# ac_thing.net
KiCad netlist of a schematic drawn in EAGLE
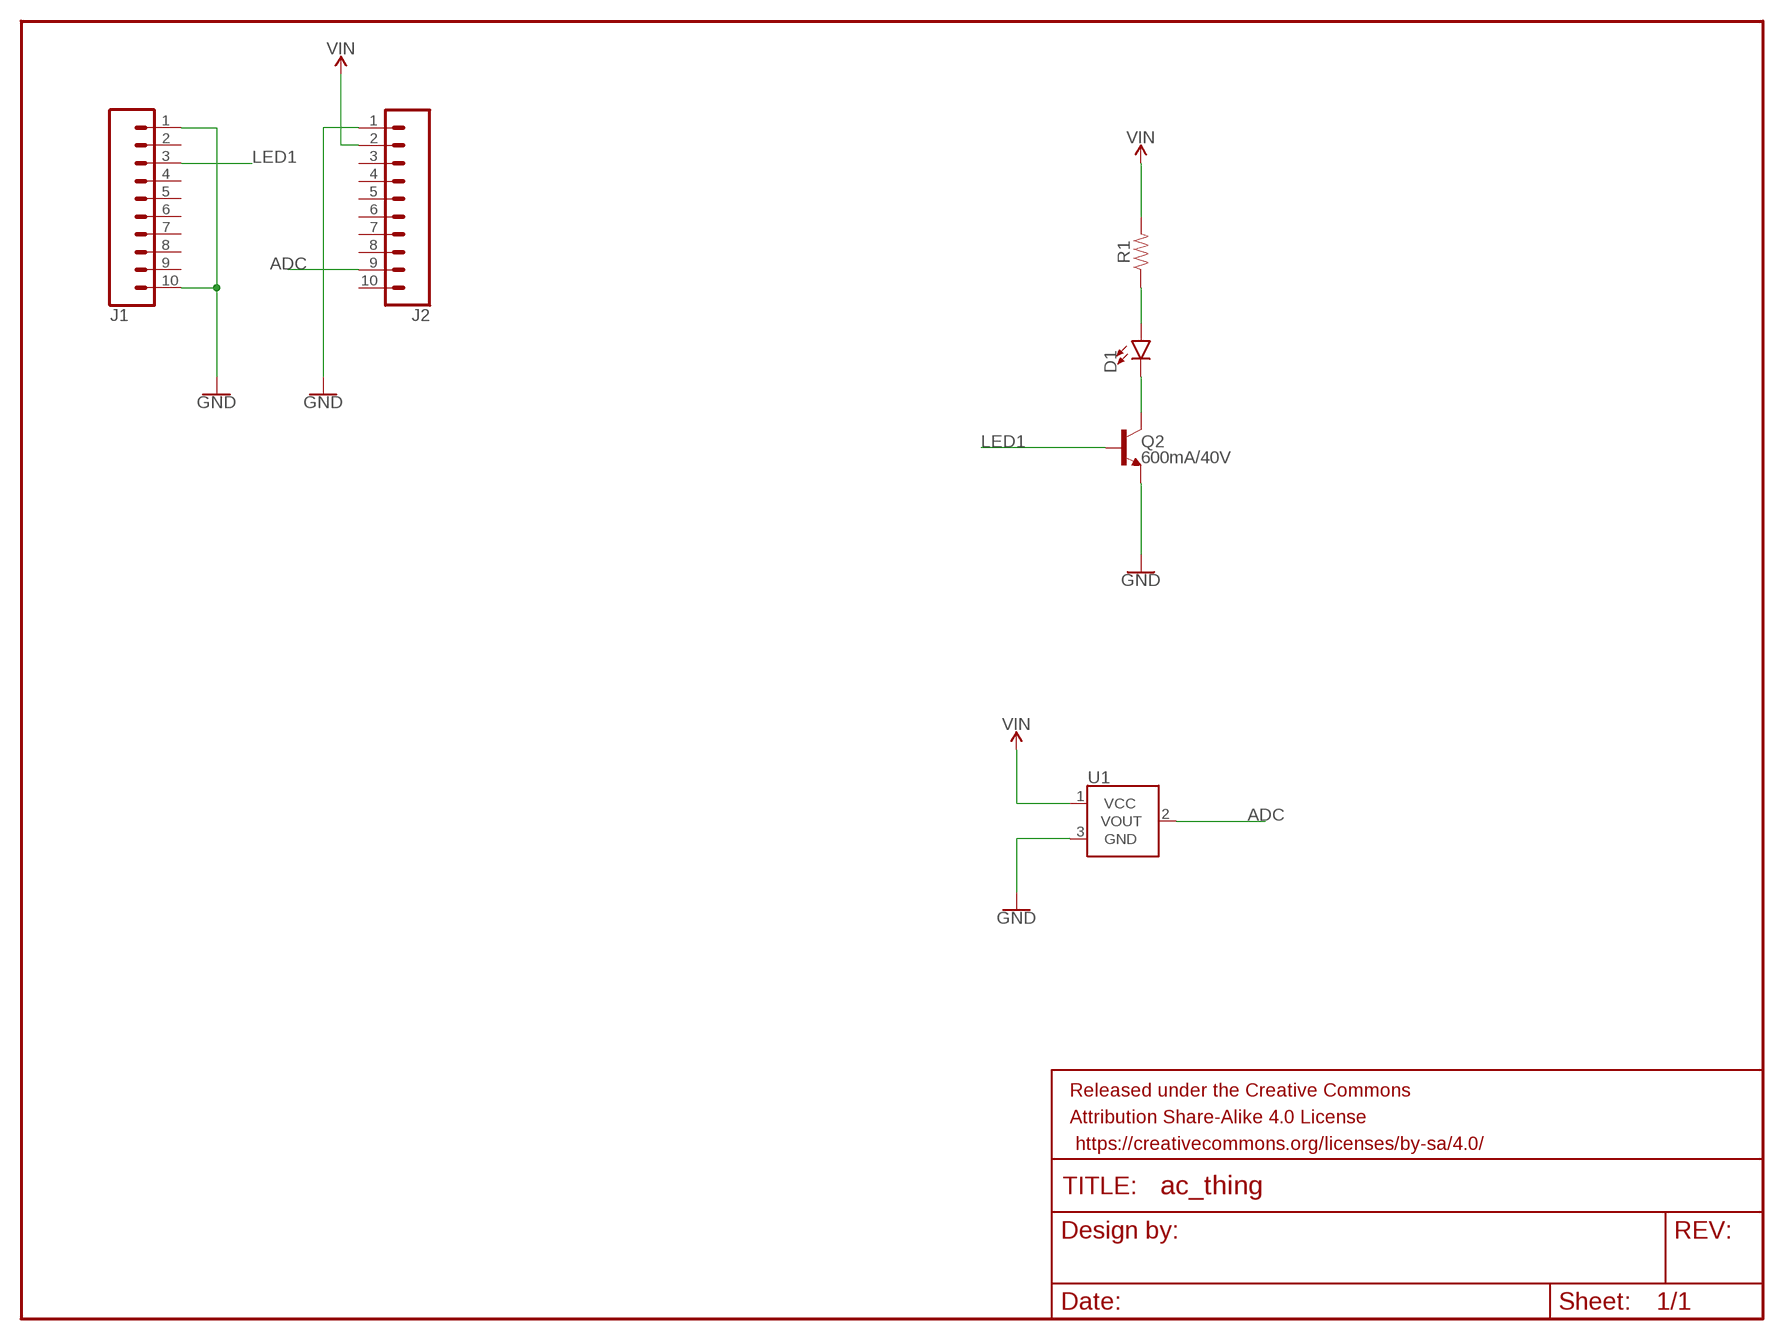
[diagram p0: schematic, sheet 1]

(export (version "E")
  (design (tool "Eeschema 10.0.6"))
  (components
    (comp (ref "D1")
      (value "LED5MM")
      (footprint "eagle-import:LED_5MM")
      (libsource (lib "eagle-import") (part "LED5MM"))
    )
    (comp (ref "FRAME1")
      (value "FRAME-LETTER")
      (footprint "eagle-import:CREATIVE_COMMONS")
      (libsource (lib "eagle-import") (part "FRAME-LETTER"))
    )
    (comp (ref "J1")
      (value "CONN_10NO_SILK_PTH_FEMALE")
      (footprint "eagle-import:1X10_NO_SILK")
      (libsource (lib "eagle-import") (part "CONN_10NO_SILK_PTH_FEMALE"))
    )
    (comp (ref "J2")
      (value "CONN_10NO_SILK_PTH_FEMALE")
      (footprint "eagle-import:1X10_NO_SILK")
      (libsource (lib "eagle-import") (part "CONN_10NO_SILK_PTH_FEMALE"))
    )
    (comp (ref "Q2")
      (value "600mA/40V")
      (footprint "eagle-import:TO-92")
      (libsource (lib "eagle-import") (part "TRANS_NPN-P2N2222A"))
    )
    (comp (ref "R1")
      (value "RESISTORAXIAL-0.3")
      (footprint "eagle-import:AXIAL-0.3")
      (libsource (lib "eagle-import") (part "RESISTORAXIAL-0.3"))
    )
    (comp (ref "U1")
      (value "TMP36GT9")
      (footprint "eagle-import:TO-92")
      (libsource (lib "eagle-import") (part "TMP36GT9"))
    )
  )
  (nets
    (net (code "1") (name "/ADC") (class "Default")
      (node (ref "J2") (pin "9") (pinfunction "9_9") (pintype "passive"))
      (node (ref "U1") (pin "2") (pinfunction "VOUT_2") (pintype "bidirectional"))
    )
    (net (code "2") (name "/LED1") (class "Default")
      (node (ref "J1") (pin "3") (pinfunction "3_3") (pintype "passive"))
      (node (ref "Q2") (pin "2") (pinfunction "B_2") (pintype "passive"))
    )
    (net (code "3") (name "GND") (class "Default")
      (node (ref "J1") (pin "1") (pinfunction "1_1") (pintype "passive"))
      (node (ref "J1") (pin "10") (pinfunction "10_10") (pintype "passive"))
      (node (ref "J2") (pin "1") (pinfunction "1_1") (pintype "passive"))
      (node (ref "Q2") (pin "3") (pinfunction "E_3") (pintype "passive"))
      (node (ref "U1") (pin "3") (pinfunction "GND_3") (pintype "bidirectional"))
    )
    (net (code "4") (name "Net-(D1-C)") (class "Default")
      (node (ref "D1") (pin "K") (pinfunction "C_K") (pintype "passive"))
      (node (ref "Q2") (pin "1") (pinfunction "C_1") (pintype "passive"))
    )
    (net (code "5") (name "Net-(R1-1)") (class "Default")
      (node (ref "D1") (pin "A") (pinfunction "A_A") (pintype "passive"))
      (node (ref "R1") (pin "P$1") (pinfunction "1_P$1") (pintype "passive"))
    )
    (net (code "6") (name "VIN") (class "Default")
      (node (ref "J2") (pin "2") (pinfunction "2_2") (pintype "passive"))
      (node (ref "R1") (pin "P$2") (pinfunction "2_P$2") (pintype "passive"))
      (node (ref "U1") (pin "1") (pinfunction "VCC_1") (pintype "bidirectional"))
    )
    (net (code "7") (name "unconnected-(J1-Pad2)") (class "Default")
      (node (ref "J1") (pin "2") (pinfunction "2_2") (pintype "passive"))
    )
    (net (code "8") (name "unconnected-(J1-Pad4)") (class "Default")
      (node (ref "J1") (pin "4") (pinfunction "4_4") (pintype "passive"))
    )
    (net (code "9") (name "unconnected-(J1-Pad5)") (class "Default")
      (node (ref "J1") (pin "5") (pinfunction "5_5") (pintype "passive"))
    )
    (net (code "10") (name "unconnected-(J1-Pad6)") (class "Default")
      (node (ref "J1") (pin "6") (pinfunction "6_6") (pintype "passive"))
    )
    (net (code "11") (name "unconnected-(J1-Pad7)") (class "Default")
      (node (ref "J1") (pin "7") (pinfunction "7_7") (pintype "passive"))
    )
    (net (code "12") (name "unconnected-(J1-Pad8)") (class "Default")
      (node (ref "J1") (pin "8") (pinfunction "8_8") (pintype "passive"))
    )
    (net (code "13") (name "unconnected-(J1-Pad9)") (class "Default")
      (node (ref "J1") (pin "9") (pinfunction "9_9") (pintype "passive"))
    )
    (net (code "14") (name "unconnected-(J2-Pad3)") (class "Default")
      (node (ref "J2") (pin "3") (pinfunction "3_3") (pintype "passive"))
    )
    (net (code "15") (name "unconnected-(J2-Pad4)") (class "Default")
      (node (ref "J2") (pin "4") (pinfunction "4_4") (pintype "passive"))
    )
    (net (code "16") (name "unconnected-(J2-Pad5)") (class "Default")
      (node (ref "J2") (pin "5") (pinfunction "5_5") (pintype "passive"))
    )
    (net (code "17") (name "unconnected-(J2-Pad6)") (class "Default")
      (node (ref "J2") (pin "6") (pinfunction "6_6") (pintype "passive"))
    )
    (net (code "18") (name "unconnected-(J2-Pad7)") (class "Default")
      (node (ref "J2") (pin "7") (pinfunction "7_7") (pintype "passive"))
    )
    (net (code "19") (name "unconnected-(J2-Pad8)") (class "Default")
      (node (ref "J2") (pin "8") (pinfunction "8_8") (pintype "passive"))
    )
    (net (code "20") (name "unconnected-(J2-Pad10)") (class "Default")
      (node (ref "J2") (pin "10") (pinfunction "10_10") (pintype "passive"))
    )
  )
)
